# DM3370_USB.net
KiCad netlist of a schematic drawn in Altium Designer
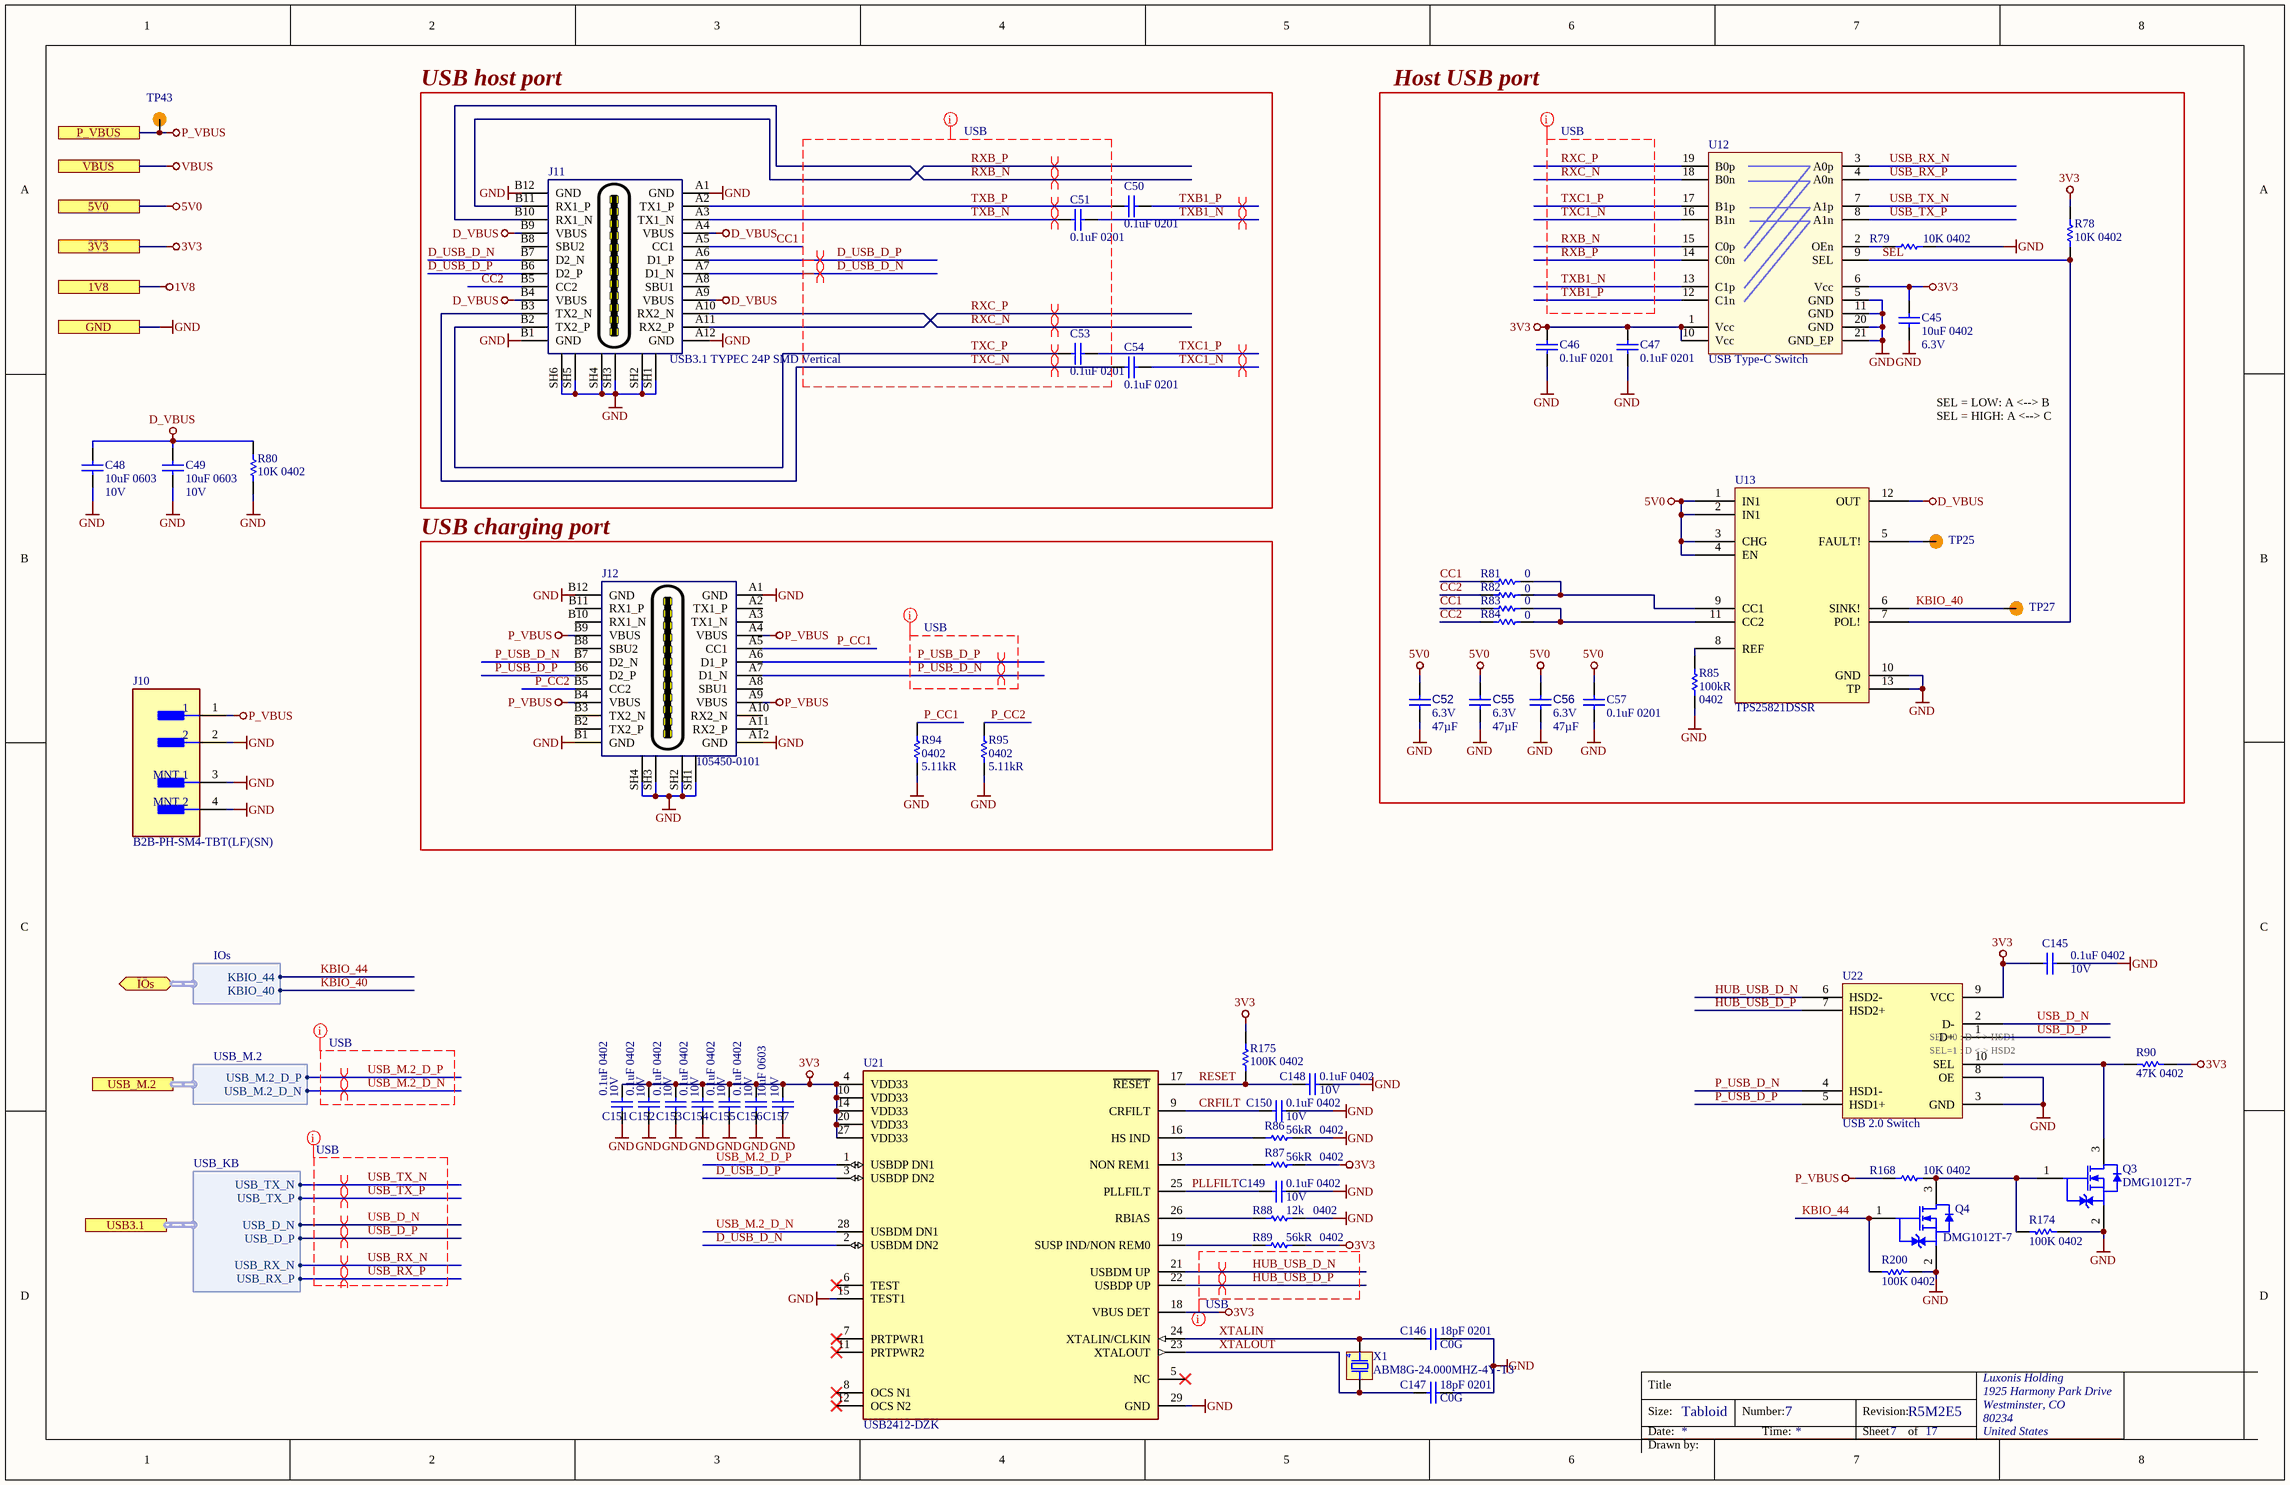
[diagram p0: DM3370_USB.SchDoc]

(export (version "E")
  (design (tool "Eeschema 10.0.6"))
  (components
    (comp (ref "C45")
      (value "10uF 0402")
      (footprint "CAP_Altium_Vault_Generic:CAPC0402(1005)70_L")
      (description "CAP CER 10UF 6.3V X5R 0402 20%")
      (fields (field (name "TOLERANCE") "20%") (field (name "VOLTAGE RATING") "6.3V"))
      (libsource (lib "LuxonisMaster") (part "GRM155R60J106ME15D"))
    )
    (comp (ref "C46")
      (value "0.1uF 0201")
      (footprint "CAP_Altium_Vault_Generic:CAPC0201(0603)33_L")
      (description "CAP CER 0.1UF 10V X5R 0201")
      (fields (field (name "TOLERANCE") "10%") (field (name "VOLTAGE") "10V"))
      (libsource (lib "LuxonisMaster") (part "GRM033R61A104KE15D"))
    )
    (comp (ref "C47")
      (value "0.1uF 0201")
      (footprint "CAP_Altium_Vault_Generic:CAPC0201(0603)33_L")
      (description "CAP CER 0.1UF 10V X5R 0201")
      (fields (field (name "TOLERANCE") "10%") (field (name "VOLTAGE") "10V"))
      (libsource (lib "LuxonisMaster") (part "GRM033R61A104KE15D"))
    )
    (comp (ref "C48")
      (value "10uF 0603")
      (footprint "CAP_Altium_Vault_Generic:CAPC0603(1608)100_L")
      (description "CAP CER 10UF 10V X5R 0603 20%")
      (fields (field (name "TOLERANCE") "20%") (field (name "VOLTAGE RATING") "10V"))
      (libsource (lib "LuxonisMaster") (part "GRM188R61A106ME69D"))
    )
    (comp (ref "C49")
      (value "10uF 0603")
      (footprint "CAP_Altium_Vault_Generic:CAPC0603(1608)100_L")
      (description "CAP CER 10UF 10V X5R 0603 20%")
      (fields (field (name "TOLERANCE") "20%") (field (name "VOLTAGE RATING") "10V"))
      (libsource (lib "LuxonisMaster") (part "GRM188R61A106ME69D"))
    )
    (comp (ref "C50")
      (value "0.1uF 0201")
      (footprint "CAP_Altium_Vault_Generic:CAPC0201(0603)33_L")
      (description "CAP CER 0.1UF 10V X5R 0201")
      (fields (field (name "TOLERANCE") "10%") (field (name "VOLTAGE") "10V"))
      (libsource (lib "LuxonisMaster") (part "GRM033R61A104KE15D"))
    )
    (comp (ref "C51")
      (value "0.1uF 0201")
      (footprint "CAP_Altium_Vault_Generic:CAPC0201(0603)33_L")
      (description "CAP CER 0.1UF 10V X5R 0201")
      (fields (field (name "TOLERANCE") "10%") (field (name "VOLTAGE") "10V"))
      (libsource (lib "LuxonisMaster") (part "GRM033R61A104KE15D"))
    )
    (comp (ref "C52")
      (value "47µF")
      (footprint "CAPC0805(2012)145_L")
      (description "CAP CER 47UF 6.3V X5R 0805 10%")
      (fields
        (field (name "VOLTAGE RATING") "6.3V")
        (field (name "TOLERANCE") "10%")
        (field (name "Comment") "C0805C476M9PACTU")
      )
      (libsource (lib "Luxonis LLC") (part "*"))
    )
    (comp (ref "C53")
      (value "0.1uF 0201")
      (footprint "CAP_Altium_Vault_Generic:CAPC0201(0603)33_L")
      (description "CAP CER 0.1UF 10V X5R 0201")
      (fields (field (name "TOLERANCE") "10%") (field (name "VOLTAGE") "10V"))
      (libsource (lib "LuxonisMaster") (part "GRM033R61A104KE15D"))
    )
    (comp (ref "C54")
      (value "0.1uF 0201")
      (footprint "CAP_Altium_Vault_Generic:CAPC0201(0603)33_L")
      (description "CAP CER 0.1UF 10V X5R 0201")
      (fields (field (name "TOLERANCE") "10%") (field (name "VOLTAGE") "10V"))
      (libsource (lib "LuxonisMaster") (part "GRM033R61A104KE15D"))
    )
    (comp (ref "C55")
      (value "47µF")
      (footprint "CAPC0805(2012)145_L")
      (description "CAP CER 47UF 6.3V X5R 0805 10%")
      (fields
        (field (name "VOLTAGE RATING") "6.3V")
        (field (name "TOLERANCE") "10%")
        (field (name "Comment") "C0805C476M9PACTU")
      )
      (libsource (lib "Luxonis LLC") (part "*"))
    )
    (comp (ref "C56")
      (value "47µF")
      (footprint "CAPC0805(2012)145_L")
      (description "CAP CER 47UF 6.3V X5R 0805 10%")
      (fields
        (field (name "VOLTAGE RATING") "6.3V")
        (field (name "TOLERANCE") "10%")
        (field (name "Comment") "C0805C476M9PACTU")
      )
      (libsource (lib "Luxonis LLC") (part "*"))
    )
    (comp (ref "C57")
      (value "0.1uF 0201")
      (footprint "CAP_Altium_Vault_Generic:CAPC0201(0603)33_L")
      (description "CAP CER 0.1UF 10V X5R 0201")
      (fields (field (name "TOLERANCE") "10%") (field (name "VOLTAGE") "10V"))
      (libsource (lib "LuxonisMaster") (part "GRM033R61A104KE15D"))
    )
    (comp (ref "C145")
      (value "0.1uF 0402")
      (footprint "CAP_Altium_Vault_Generic:CAPC0402(1005)70_L")
      (description "CAP CER 0.1UF 10V X7R 0402 5%")
      (fields (field (name "TOLERANCE") "5%") (field (name "VOLTAGE RATING") "10V"))
      (libsource (lib "LuxonisMaster") (part "GRM155R71A104JA01D"))
    )
    (comp (ref "C146")
      (value "18pF 0201")
      (footprint "CAP_Altium_Vault_Generic:CAPC0201(0603)33_L")
      (description "Cap Ceramic 18pF 25V C0G 1% Pad SMD 0201 125C T/R")
      (fields (field (name "TOLERANCE") "1%") (field (name "DIELECTRIC") "C0G"))
      (libsource (lib "DM1092_R0M0E0") (part "GRM0335C1E180FA01D"))
    )
    (comp (ref "C147")
      (value "18pF 0201")
      (footprint "CAP_Altium_Vault_Generic:CAPC0201(0603)33_L")
      (description "Cap Ceramic 18pF 25V C0G 1% Pad SMD 0201 125C T/R")
      (fields (field (name "TOLERANCE") "1%") (field (name "DIELECTRIC") "C0G"))
      (libsource (lib "DM1092_R0M0E0") (part "GRM0335C1E180FA01D"))
    )
    (comp (ref "C148")
      (value "0.1uF 0402")
      (footprint "CAP_Altium_Vault_Generic:CAPC0402(1005)70_L")
      (description "CAP CER 0.1UF 10V X7R 0402 5%")
      (fields (field (name "TOLERANCE") "5%") (field (name "VOLTAGE RATING") "10V"))
      (libsource (lib "LuxonisMaster") (part "GRM155R71A104JA01D"))
    )
    (comp (ref "C149")
      (value "0.1uF 0402")
      (footprint "CAP_Altium_Vault_Generic:CAPC0402(1005)70_L")
      (description "CAP CER 0.1UF 10V X7R 0402 5%")
      (fields (field (name "TOLERANCE") "5%") (field (name "VOLTAGE RATING") "10V"))
      (libsource (lib "LuxonisMaster") (part "GRM155R71A104JA01D"))
    )
    (comp (ref "C150")
      (value "0.1uF 0402")
      (footprint "CAP_Altium_Vault_Generic:CAPC0402(1005)70_L")
      (description "CAP CER 0.1UF 10V X7R 0402 5%")
      (fields (field (name "TOLERANCE") "5%") (field (name "VOLTAGE RATING") "10V"))
      (libsource (lib "LuxonisMaster") (part "GRM155R71A104JA01D"))
    )
    (comp (ref "C151")
      (value "0.1uF 0402")
      (footprint "CAP_Altium_Vault_Generic:CAPC0402(1005)70_L")
      (description "CAP CER 0.1UF 10V X7R 0402 5%")
      (fields (field (name "TOLERANCE") "5%") (field (name "VOLTAGE RATING") "10V"))
      (libsource (lib "LuxonisMaster") (part "GRM155R71A104JA01D"))
    )
    (comp (ref "C152")
      (value "0.1uF 0402")
      (footprint "CAP_Altium_Vault_Generic:CAPC0402(1005)70_L")
      (description "CAP CER 0.1UF 10V X7R 0402 5%")
      (fields (field (name "TOLERANCE") "5%") (field (name "VOLTAGE RATING") "10V"))
      (libsource (lib "LuxonisMaster") (part "GRM155R71A104JA01D"))
    )
    (comp (ref "C153")
      (value "0.1uF 0402")
      (footprint "CAP_Altium_Vault_Generic:CAPC0402(1005)70_L")
      (description "CAP CER 0.1UF 10V X7R 0402 5%")
      (fields (field (name "TOLERANCE") "5%") (field (name "VOLTAGE RATING") "10V"))
      (libsource (lib "LuxonisMaster") (part "GRM155R71A104JA01D"))
    )
    (comp (ref "C154")
      (value "0.1uF 0402")
      (footprint "CAP_Altium_Vault_Generic:CAPC0402(1005)70_L")
      (description "CAP CER 0.1UF 10V X7R 0402 5%")
      (fields (field (name "TOLERANCE") "5%") (field (name "VOLTAGE RATING") "10V"))
      (libsource (lib "LuxonisMaster") (part "GRM155R71A104JA01D"))
    )
    (comp (ref "C155")
      (value "0.1uF 0402")
      (footprint "CAP_Altium_Vault_Generic:CAPC0402(1005)70_L")
      (description "CAP CER 0.1UF 10V X7R 0402 5%")
      (fields (field (name "TOLERANCE") "5%") (field (name "VOLTAGE RATING") "10V"))
      (libsource (lib "LuxonisMaster") (part "GRM155R71A104JA01D"))
    )
    (comp (ref "C156")
      (value "0.1uF 0402")
      (footprint "CAP_Altium_Vault_Generic:CAPC0402(1005)70_L")
      (description "CAP CER 0.1UF 10V X7R 0402 5%")
      (fields (field (name "TOLERANCE") "5%") (field (name "VOLTAGE RATING") "10V"))
      (libsource (lib "LuxonisMaster") (part "GRM155R71A104JA01D"))
    )
    (comp (ref "C157")
      (value "10uF 0603")
      (footprint "CAP_Altium_Vault_Generic:CAPC0603(1608)100_L")
      (description "CAP CER 10UF 10V X5R 0603 20%")
      (fields (field (name "TOLERANCE") "20%") (field (name "VOLTAGE RATING") "10V"))
      (libsource (lib "LuxonisMaster") (part "GRM188R61A106ME69D"))
    )
    (comp (ref "J10")
      (value "B2B-PH-SM4-TBT(LF)(SN)")
      (footprint "FP-B2B-PH-SM4-TBT_LF_SN-MFG")
      (libsource (lib "Luxonis LLC") (part "56ec3178a87b3978bdc1b3682cd516a"))
    )
    (comp (ref "J11")
      (value "USB3.1 TYPEC 24P SMD Vertical")
      (footprint "CX80B1-24P")
      (description "CONN RCPT USB3.1 TYPEC 24POS SMD Vertical")
      (libsource (lib "LuxonisMaster") (part "CX80B1-24P"))
    )
    (comp (ref "J12")
      (value "105450-0101")
      (footprint "105450-0101")
      (description "CONN RCP USB3.1 TYPEC 24P SMD RA")
      (libsource (lib "Luxonis LLC") (part "105450-0101"))
    )
    (comp (ref "Q3")
      (value "DMG1012T-7")
      (footprint "LuxonisMaster:DMG1012T-7")
      (description "MOSFET N-CH 20V 630MA SOT-523")
      (libsource (lib "LuxonisMaster") (part "DMG1012T-7"))
    )
    (comp (ref "Q4")
      (value "DMG1012T-7")
      (footprint "LuxonisMaster:DMG1012T-7")
      (description "MOSFET N-CH 20V 630MA SOT-523")
      (libsource (lib "LuxonisMaster") (part "DMG1012T-7"))
    )
    (comp (ref "R78")
      (value "10K 0402")
      (footprint "RES_Altium_Vault_Generic:RESC0402(1005)_L")
      (fields (field (name "TOLERANCE") "1%"))
      (libsource (lib "LuxonisMaster") (part "RC0402FR-1310KL"))
    )
    (comp (ref "R79")
      (value "10K 0402")
      (footprint "RES_Altium_Vault_Generic:RESC0402(1005)_L")
      (fields (field (name "TOLERANCE") "1%"))
      (libsource (lib "LuxonisMaster") (part "RC0402FR-1310KL"))
    )
    (comp (ref "R80")
      (value "10K 0402")
      (footprint "RES_Altium_Vault_Generic:RESC0402(1005)_L")
      (fields (field (name "TOLERANCE") "1%"))
      (libsource (lib "LuxonisMaster") (part "RC0402FR-1310KL"))
    )
    (comp (ref "R81")
      (value "0")
      (footprint "RESC0402(1005)_L")
      (description "RES SMD 0 OHM JUMPER 1/16W 0402")
      (fields (field (name "TOLERANCE") "5%") (field (name "Comment") "CRCW04020000Z0ED"))
      (libsource (lib "Luxonis LLC") (part "CR0402-FX-2492GLF"))
    )
    (comp (ref "R82")
      (value "0")
      (footprint "RESC0402(1005)_L")
      (description "RES SMD 0 OHM JUMPER 1/16W 0402")
      (fields (field (name "TOLERANCE") "5%") (field (name "Comment") "CRCW04020000Z0ED"))
      (libsource (lib "Luxonis LLC") (part "CR0402-FX-2492GLF"))
    )
    (comp (ref "R83")
      (value "0")
      (footprint "RESC0402(1005)_L")
      (description "RES SMD 0 OHM JUMPER 1/16W 0402")
      (fields (field (name "TOLERANCE") "5%") (field (name "Comment") "CRCW04020000Z0ED"))
      (libsource (lib "Luxonis LLC") (part "CR0402-FX-2492GLF"))
    )
    (comp (ref "R84")
      (value "0")
      (footprint "RESC0402(1005)_L")
      (description "RES SMD 0 OHM JUMPER 1/16W 0402")
      (fields (field (name "TOLERANCE") "5%") (field (name "Comment") "CRCW04020000Z0ED"))
      (libsource (lib "Luxonis LLC") (part "CR0402-FX-2492GLF"))
    )
    (comp (ref "R85")
      (value "RC0402FR-07100KL")
      (footprint "RESC0402(1005)_L")
      (description "RES SMD 100K OHM 1% 1/16W 0402")
      (fields
        (field (name "TOLERANCE") "1%")
        (field (name "RESISTANCE") "100kR")
        (field (name "CASE/PACKAGE") "0402")
      )
      (libsource (lib "Luxonis LLC") (part "CR0402-FX-2492GLF"))
    )
    (comp (ref "R86")
      (value "RC0402FR-0756KL")
      (footprint "RESC0402(1005)_L")
      (fields
        (field (name "TOLERANCE") "1%")
        (field (name "CASE/PACKAGE") "0402")
        (field (name "MANUFACTURER") "Yageo")
        (field (name "RESISTANCE") "56kR")
      )
      (libsource (lib "Luxonis LLC") (part "CR0402-FX-2492GLF"))
    )
    (comp (ref "R87")
      (value "RC0402FR-0756KL")
      (footprint "RESC0402(1005)_L")
      (fields
        (field (name "TOLERANCE") "1%")
        (field (name "CASE/PACKAGE") "0402")
        (field (name "MANUFACTURER") "Yageo")
        (field (name "RESISTANCE") "56kR")
      )
      (libsource (lib "Luxonis LLC") (part "CR0402-FX-2492GLF"))
    )
    (comp (ref "R88")
      (value "12k")
      (footprint "RESC0402(1005)_L")
      (fields
        (field (name "TOLERANCE") "1%")
        (field (name "CASE CODE (IMPERIAL)") "0402")
        (field (name "Comment") "RC0402FR-0712KL")
      )
      (libsource (lib "Luxonis LLC") (part "CR0402-FX-2492GLF"))
    )
    (comp (ref "R89")
      (value "RC0402FR-0756KL")
      (footprint "RESC0402(1005)_L")
      (fields
        (field (name "TOLERANCE") "1%")
        (field (name "CASE/PACKAGE") "0402")
        (field (name "MANUFACTURER") "Yageo")
        (field (name "RESISTANCE") "56kR")
      )
      (libsource (lib "Luxonis LLC") (part "CR0402-FX-2492GLF"))
    )
    (comp (ref "R90")
      (value "47K 0402")
      (footprint "RES_Altium_Vault_Generic:RESC0402(1005)_L")
      (description "RES SMD 47K OHM 1% 1/16W 0402")
      (fields (field (name "TOLERANCE") "1%"))
      (libsource (lib "LuxonisMaster") (part "RC0402FR-0747KL"))
    )
    (comp (ref "R94")
      (value "RC0402FR-075K11L")
      (footprint "RESC0402(1005)_L")
      (fields
        (field (name "CASE CODE (IMPERIAL)") "0402")
        (field (name "RESISTANCE") "5.11kR")
        (field (name "TOLERANCE") "1%")
      )
      (libsource (lib "Luxonis LLC") (part "CR0402-FX-2492GLF"))
    )
    (comp (ref "R95")
      (value "RC0402FR-075K11L")
      (footprint "RESC0402(1005)_L")
      (fields
        (field (name "CASE CODE (IMPERIAL)") "0402")
        (field (name "RESISTANCE") "5.11kR")
        (field (name "TOLERANCE") "1%")
      )
      (libsource (lib "Luxonis LLC") (part "CR0402-FX-2492GLF"))
    )
    (comp (ref "R168")
      (value "10K 0402")
      (footprint "RES_Altium_Vault_Generic:RESC0402(1005)_L")
      (fields (field (name "TOLERANCE") "1%"))
      (libsource (lib "LuxonisMaster") (part "RC0402FR-1310KL"))
    )
    (comp (ref "R174")
      (value "100K 0402")
      (footprint "RES_Altium_Vault_Generic:RESC0402(1005)_L")
      (description "RES SMD 100K OHM 1% 1/16W 0402")
      (fields (field (name "TOLERANCE") "1%"))
      (libsource (lib "LuxonisMaster") (part "RC0402FR-07100KL"))
    )
    (comp (ref "R175")
      (value "100K 0402")
      (footprint "RES_Altium_Vault_Generic:RESC0402(1005)_L")
      (description "RES SMD 100K OHM 1% 1/16W 0402")
      (fields (field (name "TOLERANCE") "1%"))
      (libsource (lib "LuxonisMaster") (part "RC0402FR-07100KL"))
    )
    (comp (ref "R200")
      (value "100K 0402")
      (footprint "RES_Altium_Vault_Generic:RESC0402(1005)_L")
      (description "RES SMD 100K OHM 1% 1/16W 0402")
      (fields (field (name "TOLERANCE") "1%"))
      (libsource (lib "LuxonisMaster") (part "RC0402FR-07100KL"))
    )
    (comp (ref "TP25")
      (value "TEST_POINT")
      (footprint "TP100_200_NS")
      (libsource (lib "Luxonis LLC") (part "TEST_POINT"))
    )
    (comp (ref "TP27")
      (value "TEST_POINT")
      (footprint "TP100_200_NS")
      (libsource (lib "Luxonis LLC") (part "TEST_POINT"))
    )
    (comp (ref "TP43")
      (value "TEST_POINT")
      (footprint "TP100_200_NS")
      (libsource (lib "Luxonis LLC") (part "TEST_POINT"))
    )
    (comp (ref "U12")
      (value "USB Type-C Switch")
      (footprint "CBTL02043A")
      (libsource (lib "LuxonisMaster") (part "CBTL02043A"))
    )
    (comp (ref "U13")
      (value "TPS25821DSSR")
      (footprint "TPS25821")
      (description "USB Type-C™ source controller and 1.5A power switch")
      (libsource (lib "Luxonis LLC") (part "TPS25821"))
    )
    (comp (ref "U21")
      (value "USB2412-DZK")
      (footprint "FP-USB2412-DZK-MFG")
      (description "USB Bus Controller, CMOS")
      (libsource (lib "Luxonis LLC") (part "471ee3c24e1ade1afb7dcaf8f5f2be2"))
    )
    (comp (ref "U22")
      (value "USB 2.0 Switch")
      (footprint "LuxonisMaster:FSUSB42UMX")
      (description "IC USB SWITCH DPDT 10UMLP")
      (libsource (lib "LuxonisMaster") (part "FSUSB42UMX"))
    )
    (comp (ref "X1")
      (value "ABM8G-24.000MHZ-4Y-T3")
      (footprint "MCSJK-7U-24.00-12-30-60-B-30")
      (description "CRYSTAL 24.0000MHZ 10PF SMD")
      (libsource (lib "Luxonis LLC") (part "ABM8G-24.000MHZ-4Y-T3"))
    )
  )
  (nets
    (net (code "4") (name "/CC1") (class "Default")
      (node (ref "J11") (pin "A5") (pinfunction "CC1_A5") (pintype "passive"))
      (node (ref "R81") (pin "1") (pinfunction "1_1") (pintype "passive"))
      (node (ref "R83") (pin "1") (pinfunction "1_1") (pintype "passive"))
    )
    (net (code "5") (name "/CC2") (class "Default")
      (node (ref "J11") (pin "B5") (pinfunction "CC2_B5") (pintype "passive"))
      (node (ref "R82") (pin "1") (pinfunction "1_1") (pintype "passive"))
      (node (ref "R84") (pin "1") (pinfunction "1_1") (pintype "passive"))
    )
    (net (code "6") (name "/CRFILT") (class "Default")
      (node (ref "C150") (pin "2") (pinfunction "2_2") (pintype "passive"))
      (node (ref "U21") (pin "9") (pinfunction "CRFILT_9") (pintype "passive"))
    )
    (net (code "7") (name "/D_USB_D_N") (class "Default")
      (node (ref "J11") (pin "A7") (pinfunction "D1_N_A7") (pintype "passive"))
      (node (ref "J11") (pin "B7") (pinfunction "D2_N_B7") (pintype "passive"))
      (node (ref "U21") (pin "2") (pinfunction "USBDM_DN2_2") (pintype "bidirectional"))
    )
    (net (code "8") (name "/D_USB_D_P") (class "Default")
      (node (ref "J11") (pin "A6") (pinfunction "D1_P_A6") (pintype "passive"))
      (node (ref "J11") (pin "B6") (pinfunction "D2_P_B6") (pintype "passive"))
      (node (ref "U21") (pin "3") (pinfunction "USBDP_DN2_3") (pintype "bidirectional"))
    )
    (net (code "9") (name "/HUB_USB_D_N") (class "Default")
      (node (ref "U21") (pin "21") (pinfunction "USBDM_UP_21") (pintype "passive"))
      (node (ref "U22") (pin "6") (pinfunction "HSD2-_6") (pintype "passive"))
    )
    (net (code "10") (name "/HUB_USB_D_P") (class "Default")
      (node (ref "U21") (pin "22") (pinfunction "USBDP_UP_22") (pintype "passive"))
      (node (ref "U22") (pin "7") (pinfunction "HSD2+_7") (pintype "passive"))
    )
    (net (code "11") (name "/KBIO_40") (class "Default")
      (node (ref "TP27") (pin "1") (pintype "passive"))
      (node (ref "U13") (pin "6") (pinfunction "SINK!_6") (pintype "passive"))
    )
    (net (code "12") (name "/KBIO_44") (class "Default")
      (node (ref "Q4") (pin "1") (pinfunction "1_1") (pintype "passive"))
      (node (ref "R200") (pin "2") (pinfunction "2_2") (pintype "passive"))
    )
    (net (code "13") (name "/PLLFILT") (class "Default")
      (node (ref "C149") (pin "2") (pinfunction "2_2") (pintype "passive"))
      (node (ref "U21") (pin "25") (pinfunction "PLLFILT_25") (pintype "passive"))
    )
    (net (code "14") (name "/P_CC1") (class "Default")
      (node (ref "J12") (pin "A5") (pinfunction "CC1_A5") (pintype "passive"))
      (node (ref "R94") (pin "2") (pinfunction "2_2") (pintype "passive"))
    )
    (net (code "15") (name "/P_CC2") (class "Default")
      (node (ref "J12") (pin "B5") (pinfunction "CC2_B5") (pintype "passive"))
      (node (ref "R95") (pin "2") (pinfunction "2_2") (pintype "passive"))
    )
    (net (code "16") (name "/P_USB_D_N") (class "Default")
      (node (ref "J12") (pin "A7") (pinfunction "D1_N_A7") (pintype "passive"))
      (node (ref "J12") (pin "B7") (pinfunction "D2_N_B7") (pintype "passive"))
      (node (ref "U22") (pin "4") (pinfunction "HSD1-_4") (pintype "passive"))
    )
    (net (code "17") (name "/P_USB_D_P") (class "Default")
      (node (ref "J12") (pin "A6") (pinfunction "D1_P_A6") (pintype "passive"))
      (node (ref "J12") (pin "B6") (pinfunction "D2_P_B6") (pintype "passive"))
      (node (ref "U22") (pin "5") (pinfunction "HSD1+_5") (pintype "passive"))
    )
    (net (code "18") (name "/RESET") (class "Default")
      (node (ref "C148") (pin "2") (pinfunction "2_2") (pintype "passive"))
      (node (ref "R175") (pin "1") (pinfunction "1_1") (pintype "passive"))
      (node (ref "U21") (pin "17") (pinfunction "~{RESET}_17") (pintype "passive"))
    )
    (net (code "19") (name "/RXB_N") (class "Default")
      (node (ref "J11") (pin "B10") (pinfunction "RX1_N_B10") (pintype "passive"))
      (node (ref "U12") (pin "15") (pinfunction "C0p_15") (pintype "passive"))
    )
    (net (code "20") (name "/RXB_P") (class "Default")
      (node (ref "J11") (pin "B11") (pinfunction "RX1_P_B11") (pintype "passive"))
      (node (ref "U12") (pin "14") (pinfunction "C0n_14") (pintype "passive"))
    )
    (net (code "21") (name "/RXC_N") (class "Default")
      (node (ref "J11") (pin "A10") (pinfunction "RX2_N_A10") (pintype "passive"))
      (node (ref "U12") (pin "18") (pinfunction "B0n_18") (pintype "passive"))
    )
    (net (code "22") (name "/RXC_P") (class "Default")
      (node (ref "J11") (pin "A11") (pinfunction "RX2_P_A11") (pintype "passive"))
      (node (ref "U12") (pin "19") (pinfunction "B0p_19") (pintype "passive"))
    )
    (net (code "23") (name "/SEL") (class "Default")
      (node (ref "R78") (pin "1") (pinfunction "1_1") (pintype "passive"))
      (node (ref "U12") (pin "9") (pinfunction "SEL_9") (pintype "passive"))
      (node (ref "U13") (pin "7") (pinfunction "POL!_7") (pintype "passive"))
    )
    (net (code "24") (name "/TXB1_N") (class "Default")
      (node (ref "C51") (pin "2") (pinfunction "2_2") (pintype "passive"))
      (node (ref "U12") (pin "13") (pinfunction "C1p_13") (pintype "passive"))
    )
    (net (code "25") (name "/TXB1_P") (class "Default")
      (node (ref "C50") (pin "2") (pinfunction "2_2") (pintype "passive"))
      (node (ref "U12") (pin "12") (pinfunction "C1n_12") (pintype "passive"))
    )
    (net (code "26") (name "/TXB_N") (class "Default")
      (node (ref "C51") (pin "1") (pinfunction "1_1") (pintype "passive"))
      (node (ref "J11") (pin "A3") (pinfunction "TX1_N_A3") (pintype "passive"))
    )
    (net (code "27") (name "/TXB_P") (class "Default")
      (node (ref "C50") (pin "1") (pinfunction "1_1") (pintype "passive"))
      (node (ref "J11") (pin "A2") (pinfunction "TX1_P_A2") (pintype "passive"))
    )
    (net (code "28") (name "/TXC1_N") (class "Default")
      (node (ref "C54") (pin "2") (pinfunction "2_2") (pintype "passive"))
      (node (ref "U12") (pin "16") (pinfunction "B1n_16") (pintype "passive"))
    )
    (net (code "29") (name "/TXC1_P") (class "Default")
      (node (ref "C53") (pin "2") (pinfunction "2_2") (pintype "passive"))
      (node (ref "U12") (pin "17") (pinfunction "B1p_17") (pintype "passive"))
    )
    (net (code "30") (name "/TXC_N") (class "Default")
      (node (ref "C54") (pin "1") (pinfunction "1_1") (pintype "passive"))
      (node (ref "J11") (pin "B3") (pinfunction "TX2_N_B3") (pintype "passive"))
    )
    (net (code "31") (name "/TXC_P") (class "Default")
      (node (ref "C53") (pin "1") (pinfunction "1_1") (pintype "passive"))
      (node (ref "J11") (pin "B2") (pinfunction "TX2_P_B2") (pintype "passive"))
    )
    (net (code "32") (name "/USB_D_N") (class "Default")
      (node (ref "U22") (pin "2") (pinfunction "D-_2") (pintype "passive"))
    )
    (net (code "33") (name "/USB_D_P") (class "Default")
      (node (ref "U22") (pin "1") (pinfunction "D+_1") (pintype "passive"))
    )
    (net (code "34") (name "/USB_M.2_D_N") (class "Default")
      (node (ref "U21") (pin "28") (pinfunction "USBDM_DN1_28") (pintype "passive"))
    )
    (net (code "35") (name "/USB_M.2_D_P") (class "Default")
      (node (ref "U21") (pin "1") (pinfunction "USBDP_DN1_1") (pintype "bidirectional"))
    )
    (net (code "36") (name "/USB_RX_N") (class "Default")
      (node (ref "U12") (pin "3") (pinfunction "A0p_3") (pintype "passive"))
    )
    (net (code "37") (name "/USB_RX_P") (class "Default")
      (node (ref "U12") (pin "4") (pinfunction "A0n_4") (pintype "passive"))
    )
    (net (code "38") (name "/USB_TX_N") (class "Default")
      (node (ref "U12") (pin "7") (pinfunction "A1p_7") (pintype "passive"))
    )
    (net (code "39") (name "/USB_TX_P") (class "Default")
      (node (ref "U12") (pin "8") (pinfunction "A1n_8") (pintype "passive"))
    )
    (net (code "40") (name "/XTALIN") (class "Default")
      (node (ref "C146") (pin "1") (pinfunction "1_1") (pintype "passive"))
      (node (ref "U21") (pin "24") (pinfunction "XTALIN/CLKIN_24") (pintype "input"))
      (node (ref "X1") (pin "3") (pinfunction "OSC2_3") (pintype "passive"))
    )
    (net (code "41") (name "/XTALOUT") (class "Default")
      (node (ref "C147") (pin "1") (pinfunction "1_1") (pintype "passive"))
      (node (ref "U21") (pin "23") (pinfunction "XTALOUT_23") (pintype "output"))
      (node (ref "X1") (pin "1") (pinfunction "OSC1_1") (pintype "passive"))
    )
    (net (code "46") (name "3V3") (class "Default")
      (node (ref "C145") (pin "1") (pinfunction "1_1") (pintype "passive"))
      (node (ref "C151") (pin "2") (pinfunction "2_2") (pintype "passive"))
      (node (ref "C152") (pin "2") (pinfunction "2_2") (pintype "passive"))
      (node (ref "C153") (pin "2") (pinfunction "2_2") (pintype "passive"))
      (node (ref "C154") (pin "2") (pinfunction "2_2") (pintype "passive"))
      (node (ref "C155") (pin "2") (pinfunction "2_2") (pintype "passive"))
      (node (ref "C156") (pin "2") (pinfunction "2_2") (pintype "passive"))
      (node (ref "C157") (pin "2") (pinfunction "2_2") (pintype "passive"))
      (node (ref "C45") (pin "2") (pinfunction "2_2") (pintype "passive"))
      (node (ref "C46") (pin "2") (pinfunction "2_2") (pintype "passive"))
      (node (ref "C47") (pin "2") (pinfunction "2_2") (pintype "passive"))
      (node (ref "R175") (pin "2") (pinfunction "2_2") (pintype "passive"))
      (node (ref "R78") (pin "2") (pinfunction "2_2") (pintype "passive"))
      (node (ref "R87") (pin "2") (pinfunction "2_2") (pintype "passive"))
      (node (ref "R89") (pin "2") (pinfunction "2_2") (pintype "passive"))
      (node (ref "R90") (pin "1") (pinfunction "1_1") (pintype "passive"))
      (node (ref "U12") (pin "1") (pinfunction "Vcc_1") (pintype "passive"))
      (node (ref "U12") (pin "10") (pinfunction "Vcc_10") (pintype "passive"))
      (node (ref "U12") (pin "6") (pinfunction "Vcc_6") (pintype "passive"))
      (node (ref "U21") (pin "10") (pinfunction "VDD33_10") (pintype "power_in"))
      (node (ref "U21") (pin "14") (pinfunction "VDD33_14") (pintype "power_in"))
      (node (ref "U21") (pin "18") (pinfunction "VBUS_DET_18") (pintype "passive"))
      (node (ref "U21") (pin "20") (pinfunction "VDD33_20") (pintype "power_in"))
      (node (ref "U21") (pin "27") (pinfunction "VDD33_27") (pintype "power_in"))
      (node (ref "U21") (pin "4") (pinfunction "VDD33_4") (pintype "power_in"))
      (node (ref "U22") (pin "9") (pinfunction "VCC_9") (pintype "passive"))
    )
    (net (code "47") (name "5V0") (class "Default")
      (node (ref "C52") (pin "2") (pinfunction "2_2") (pintype "passive"))
      (node (ref "C55") (pin "2") (pinfunction "2_2") (pintype "passive"))
      (node (ref "C56") (pin "2") (pinfunction "2_2") (pintype "passive"))
      (node (ref "C57") (pin "2") (pinfunction "2_2") (pintype "passive"))
      (node (ref "U13") (pin "1") (pinfunction "IN1_1") (pintype "passive"))
      (node (ref "U13") (pin "2") (pinfunction "IN1_2") (pintype "passive"))
      (node (ref "U13") (pin "3") (pinfunction "CHG_3") (pintype "passive"))
      (node (ref "U13") (pin "4") (pinfunction "EN_4") (pintype "passive"))
    )
    (net (code "48") (name "D_VBUS") (class "Default")
      (node (ref "C48") (pin "2") (pinfunction "2_2") (pintype "passive"))
      (node (ref "C49") (pin "2") (pinfunction "2_2") (pintype "passive"))
      (node (ref "J11") (pin "A4") (pinfunction "VBUS_A4") (pintype "passive"))
      (node (ref "J11") (pin "A9") (pinfunction "VBUS_A9") (pintype "passive"))
      (node (ref "J11") (pin "B4") (pinfunction "VBUS_B4") (pintype "passive"))
      (node (ref "J11") (pin "B9") (pinfunction "VBUS_B9") (pintype "passive"))
      (node (ref "R80") (pin "2") (pinfunction "2_2") (pintype "passive"))
      (node (ref "U13") (pin "12") (pinfunction "OUT_12") (pintype "passive"))
    )
    (net (code "49") (name "GND") (class "Default")
      (node (ref "C145") (pin "2") (pinfunction "2_2") (pintype "passive"))
      (node (ref "C146") (pin "2") (pinfunction "2_2") (pintype "passive"))
      (node (ref "C147") (pin "2") (pinfunction "2_2") (pintype "passive"))
      (node (ref "C148") (pin "1") (pinfunction "1_1") (pintype "passive"))
      (node (ref "C149") (pin "1") (pinfunction "1_1") (pintype "passive"))
      (node (ref "C150") (pin "1") (pinfunction "1_1") (pintype "passive"))
      (node (ref "C151") (pin "1") (pinfunction "1_1") (pintype "passive"))
      (node (ref "C152") (pin "1") (pinfunction "1_1") (pintype "passive"))
      (node (ref "C153") (pin "1") (pinfunction "1_1") (pintype "passive"))
      (node (ref "C154") (pin "1") (pinfunction "1_1") (pintype "passive"))
      (node (ref "C155") (pin "1") (pinfunction "1_1") (pintype "passive"))
      (node (ref "C156") (pin "1") (pinfunction "1_1") (pintype "passive"))
      (node (ref "C157") (pin "1") (pinfunction "1_1") (pintype "passive"))
      (node (ref "C45") (pin "1") (pinfunction "1_1") (pintype "passive"))
      (node (ref "C46") (pin "1") (pinfunction "1_1") (pintype "passive"))
      (node (ref "C47") (pin "1") (pinfunction "1_1") (pintype "passive"))
      (node (ref "C48") (pin "1") (pinfunction "1_1") (pintype "passive"))
      (node (ref "C49") (pin "1") (pinfunction "1_1") (pintype "passive"))
      (node (ref "C52") (pin "1") (pinfunction "1_1") (pintype "passive"))
      (node (ref "C55") (pin "1") (pinfunction "1_1") (pintype "passive"))
      (node (ref "C56") (pin "1") (pinfunction "1_1") (pintype "passive"))
      (node (ref "C57") (pin "1") (pinfunction "1_1") (pintype "passive"))
      (node (ref "J10") (pin "2") (pinfunction "2_2") (pintype "passive"))
      (node (ref "J10") (pin "3") (pinfunction "MNT_1_3") (pintype "passive"))
      (node (ref "J10") (pin "4") (pinfunction "MNT_2_4") (pintype "passive"))
      (node (ref "J11") (pin "A1") (pinfunction "GND_A1") (pintype "passive"))
      (node (ref "J11") (pin "A12") (pinfunction "GND_A12") (pintype "passive"))
      (node (ref "J11") (pin "B1") (pinfunction "GND_B1") (pintype "passive"))
      (node (ref "J11") (pin "B12") (pinfunction "GND_B12") (pintype "passive"))
      (node (ref "J11") (pin "SH1") (pinfunction "SH_SH1") (pintype "passive"))
      (node (ref "J11") (pin "SH2") (pinfunction "SH_SH2") (pintype "passive"))
      (node (ref "J11") (pin "SH3") (pinfunction "SH_SH3") (pintype "passive"))
      (node (ref "J11") (pin "SH4") (pinfunction "SH_SH4") (pintype "passive"))
      (node (ref "J11") (pin "SH5") (pinfunction "SH_SH5") (pintype "passive"))
      (node (ref "J11") (pin "SH6") (pinfunction "SH_SH6") (pintype "passive"))
      (node (ref "J12") (pin "A1") (pinfunction "GND_A1") (pintype "passive"))
      (node (ref "J12") (pin "A12") (pinfunction "GND_A12") (pintype "passive"))
      (node (ref "J12") (pin "B1") (pinfunction "GND_B1") (pintype "passive"))
      (node (ref "J12") (pin "B12") (pinfunction "GND_B12") (pintype "passive"))
      (node (ref "J12") (pin "SH1") (pinfunction "SH_SH1") (pintype "passive"))
      (node (ref "J12") (pin "SH2") (pinfunction "SH_SH2") (pintype "passive"))
      (node (ref "J12") (pin "SH3") (pinfunction "SH_SH3") (pintype "passive"))
      (node (ref "J12") (pin "SH4") (pinfunction "SH_SH4") (pintype "passive"))
      (node (ref "Q3") (pin "2") (pinfunction "2_2") (pintype "passive"))
      (node (ref "Q4") (pin "2") (pinfunction "2_2") (pintype "passive"))
      (node (ref "R174") (pin "1") (pinfunction "1_1") (pintype "passive"))
      (node (ref "R200") (pin "1") (pinfunction "1_1") (pintype "passive"))
      (node (ref "R79") (pin "2") (pinfunction "2_2") (pintype "passive"))
      (node (ref "R80") (pin "1") (pinfunction "1_1") (pintype "passive"))
      (node (ref "R85") (pin "1") (pinfunction "1_1") (pintype "passive"))
      (node (ref "R86") (pin "2") (pinfunction "2_2") (pintype "passive"))
      (node (ref "R88") (pin "2") (pinfunction "2_2") (pintype "passive"))
      (node (ref "R94") (pin "1") (pinfunction "1_1") (pintype "passive"))
      (node (ref "R95") (pin "1") (pinfunction "1_1") (pintype "passive"))
      (node (ref "U12") (pin "11") (pinfunction "GND_11") (pintype "passive"))
      (node (ref "U12") (pin "20") (pinfunction "GND_20") (pintype "passive"))
      (node (ref "U12") (pin "21") (pinfunction "GND_EP_21") (pintype "passive"))
      (node (ref "U12") (pin "5") (pinfunction "GND_5") (pintype "passive"))
      (node (ref "U13") (pin "10") (pinfunction "GND_10") (pintype "passive"))
      (node (ref "U13") (pin "13") (pinfunction "TP_13") (pintype "passive"))
      (node (ref "U21") (pin "15") (pinfunction "TEST1_15") (pintype "passive"))
      (node (ref "U21") (pin "29") (pinfunction "GND_29") (pintype "power_in"))
      (node (ref "U22") (pin "3") (pinfunction "GND_3") (pintype "passive"))
      (node (ref "U22") (pin "8") (pinfunction "OE_8") (pintype "passive"))
    )
    (net (code "50") (name "Net-(Q3-Pad1)") (class "Default")
      (node (ref "Q3") (pin "1") (pinfunction "1_1") (pintype "passive"))
      (node (ref "Q4") (pin "3") (pinfunction "3_3") (pintype "passive"))
      (node (ref "R168") (pin "2") (pinfunction "2_2") (pintype "passive"))
      (node (ref "R174") (pin "2") (pinfunction "2_2") (pintype "passive"))
    )
    (net (code "51") (name "Net-(U12-OEn)") (class "Default")
      (node (ref "R79") (pin "1") (pinfunction "1_1") (pintype "passive"))
      (node (ref "U12") (pin "2") (pinfunction "OEn_2") (pintype "passive"))
    )
    (net (code "52") (name "Net-(U13-CC1)") (class "Default")
      (node (ref "R81") (pin "2") (pinfunction "2_2") (pintype "passive"))
      (node (ref "R82") (pin "2") (pinfunction "2_2") (pintype "passive"))
      (node (ref "U13") (pin "9") (pinfunction "CC1_9") (pintype "passive"))
    )
    (net (code "53") (name "Net-(U13-CC2)") (class "Default")
      (node (ref "R83") (pin "2") (pinfunction "2_2") (pintype "passive"))
      (node (ref "R84") (pin "2") (pinfunction "2_2") (pintype "passive"))
      (node (ref "U13") (pin "11") (pinfunction "CC2_11") (pintype "passive"))
    )
    (net (code "54") (name "Net-(U13-FAULT!)") (class "Default")
      (node (ref "TP25") (pin "1") (pintype "passive"))
      (node (ref "U13") (pin "5") (pinfunction "FAULT!_5") (pintype "passive"))
    )
    (net (code "55") (name "Net-(U13-REF)") (class "Default")
      (node (ref "R85") (pin "2") (pinfunction "2_2") (pintype "passive"))
      (node (ref "U13") (pin "8") (pinfunction "REF_8") (pintype "passive"))
    )
    (net (code "56") (name "Net-(U21-HS_IND)") (class "Default")
      (node (ref "R86") (pin "1") (pinfunction "1_1") (pintype "passive"))
      (node (ref "U21") (pin "16") (pinfunction "HS_IND_16") (pintype "passive"))
    )
    (net (code "57") (name "Net-(U21-NON_REM1)") (class "Default")
      (node (ref "R87") (pin "1") (pinfunction "1_1") (pintype "passive"))
      (node (ref "U21") (pin "13") (pinfunction "NON_REM1_13") (pintype "passive"))
    )
    (net (code "58") (name "Net-(U21-RBIAS)") (class "Default")
      (node (ref "R88") (pin "1") (pinfunction "1_1") (pintype "passive"))
      (node (ref "U21") (pin "26") (pinfunction "RBIAS_26") (pintype "passive"))
    )
    (net (code "59") (name "Net-(U21-SUSP_IND{slash}NON_REM0)") (class "Default")
      (node (ref "R89") (pin "1") (pinfunction "1_1") (pintype "passive"))
      (node (ref "U21") (pin "19") (pinfunction "SUSP_IND/NON_REM0_19") (pintype "passive"))
    )
    (net (code "60") (name "Net-(U22-SEL)") (class "Default")
      (node (ref "Q3") (pin "3") (pinfunction "3_3") (pintype "passive"))
      (node (ref "R90") (pin "2") (pinfunction "2_2") (pintype "passive"))
      (node (ref "U22") (pin "10") (pinfunction "SEL_10") (pintype "passive"))
    )
    (net (code "61") (name "P_VBUS") (class "Default")
      (node (ref "J10") (pin "1") (pinfunction "1_1") (pintype "passive"))
      (node (ref "J12") (pin "A4") (pinfunction "VBUS_A4") (pintype "passive"))
      (node (ref "J12") (pin "A9") (pinfunction "VBUS_A9") (pintype "passive"))
      (node (ref "J12") (pin "B4") (pinfunction "VBUS_B4") (pintype "passive"))
      (node (ref "J12") (pin "B9") (pinfunction "VBUS_B9") (pintype "passive"))
      (node (ref "R168") (pin "1") (pinfunction "1_1") (pintype "passive"))
      (node (ref "TP43") (pin "1") (pintype "passive"))
    )
    (net (code "63") (name "unconnected-(J11-SBU1-PadA8)") (class "Default")
      (node (ref "J11") (pin "A8") (pinfunction "SBU1_A8") (pintype "passive"))
    )
    (net (code "64") (name "unconnected-(J11-SBU2-PadB8)") (class "Default")
      (node (ref "J11") (pin "B8") (pinfunction "SBU2_B8") (pintype "passive"))
    )
    (net (code "65") (name "unconnected-(J12-RX1_N-PadB10)") (class "Default")
      (node (ref "J12") (pin "B10") (pinfunction "RX1_N_B10") (pintype "passive"))
    )
    (net (code "66") (name "unconnected-(J12-RX1_P-PadB11)") (class "Default")
      (node (ref "J12") (pin "B11") (pinfunction "RX1_P_B11") (pintype "passive"))
    )
    (net (code "67") (name "unconnected-(J12-RX2_N-PadA10)") (class "Default")
      (node (ref "J12") (pin "A10") (pinfunction "RX2_N_A10") (pintype "passive"))
    )
    (net (code "68") (name "unconnected-(J12-RX2_P-PadA11)") (class "Default")
      (node (ref "J12") (pin "A11") (pinfunction "RX2_P_A11") (pintype "passive"))
    )
    (net (code "69") (name "unconnected-(J12-SBU1-PadA8)") (class "Default")
      (node (ref "J12") (pin "A8") (pinfunction "SBU1_A8") (pintype "passive"))
    )
    (net (code "70") (name "unconnected-(J12-SBU2-PadB8)") (class "Default")
      (node (ref "J12") (pin "B8") (pinfunction "SBU2_B8") (pintype "passive"))
    )
    (net (code "71") (name "unconnected-(J12-TX1_N-PadA3)") (class "Default")
      (node (ref "J12") (pin "A3") (pinfunction "TX1_N_A3") (pintype "passive"))
    )
    (net (code "72") (name "unconnected-(J12-TX1_P-PadA2)") (class "Default")
      (node (ref "J12") (pin "A2") (pinfunction "TX1_P_A2") (pintype "passive"))
    )
    (net (code "73") (name "unconnected-(J12-TX2_N-PadB3)") (class "Default")
      (node (ref "J12") (pin "B3") (pinfunction "TX2_N_B3") (pintype "passive"))
    )
    (net (code "74") (name "unconnected-(J12-TX2_P-PadB2)") (class "Default")
      (node (ref "J12") (pin "B2") (pinfunction "TX2_P_B2") (pintype "passive"))
    )
    (net (code "75") (name "unconnected-(U21-NC-Pad5)") (class "Default")
      (node (ref "U21") (pin "5") (pinfunction "NC_5") (pintype "passive+no_connect"))
    )
    (net (code "76") (name "unconnected-(U21-OCS_N1-Pad8)") (class "Default")
      (node (ref "U21") (pin "8") (pinfunction "OCS_N1_8") (pintype "passive+no_connect"))
    )
    (net (code "77") (name "unconnected-(U21-OCS_N2-Pad12)") (class "Default")
      (node (ref "U21") (pin "12") (pinfunction "OCS_N2_12") (pintype "passive+no_connect"))
    )
    (net (code "78") (name "unconnected-(U21-PRTPWR1-Pad7)") (class "Default")
      (node (ref "U21") (pin "7") (pinfunction "PRTPWR1_7") (pintype "passive+no_connect"))
    )
    (net (code "79") (name "unconnected-(U21-PRTPWR2-Pad11)") (class "Default")
      (node (ref "U21") (pin "11") (pinfunction "PRTPWR2_11") (pintype "passive+no_connect"))
    )
    (net (code "80") (name "unconnected-(U21-TEST-Pad6)") (class "Default")
      (node (ref "U21") (pin "6") (pinfunction "TEST_6") (pintype "passive+no_connect"))
    )
    (net (code "81") (name "unconnected-(X1-GND-Pad2)") (class "Default")
      (node (ref "X1") (pin "2") (pinfunction "GND_2") (pintype "passive"))
    )
    (net (code "82") (name "unconnected-(X1-GND-Pad4)") (class "Default")
      (node (ref "X1") (pin "4") (pinfunction "GND_4") (pintype "passive"))
    )
  )
)
